# 5_to_12v_stepup.net
KiCad netlist of a schematic drawn in EAGLE
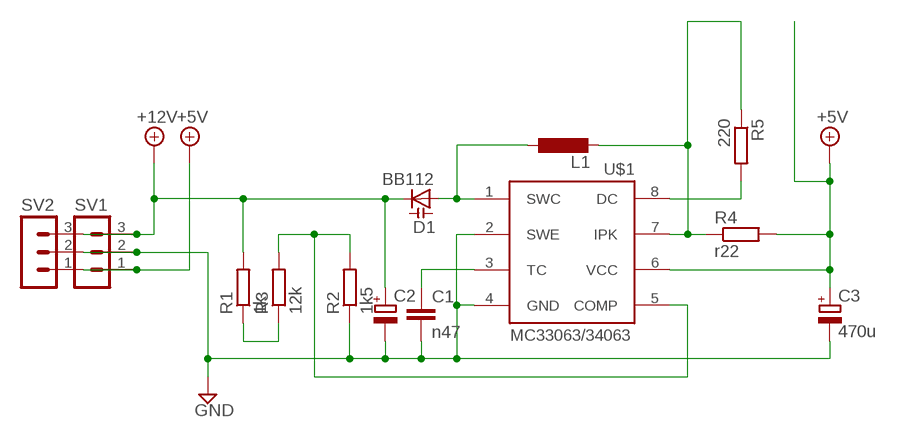
[diagram p0: schematic, sheet 1]

(export (version "E")
  (design (tool "Eeschema 10.0.6"))
  (components
    (comp (ref "C1")
      (value "n47")
      (footprint "eagle-import:C025-025X050")
      (libsource (lib "eagle-import") (part "C-EU025-025X050"))
    )
    (comp (ref "C2")
      (value "CPOL-EUE3.5-8")
      (footprint "eagle-import:E3,5-8")
      (libsource (lib "eagle-import") (part "CPOL-EUE3.5-8"))
    )
    (comp (ref "C3")
      (value "470u")
      (footprint "eagle-import:E3,5-8")
      (libsource (lib "eagle-import") (part "CPOL-EUE3.5-8"))
    )
    (comp (ref "D1")
      (value "BB112")
      (footprint "eagle-import:SOT54H")
      (libsource (lib "eagle-import") (part "BB112"))
    )
    (comp (ref "L1")
      (value "L-EU0207/2V")
      (footprint "eagle-import:0207_2V")
      (libsource (lib "eagle-import") (part "L-EU0207/2V"))
    )
    (comp (ref "R1")
      (value "1k")
      (footprint "eagle-import:0207_2V")
      (libsource (lib "eagle-import") (part "R-EU_0207/2V"))
    )
    (comp (ref "R2")
      (value "1k5")
      (footprint "eagle-import:0207_2V")
      (libsource (lib "eagle-import") (part "R-EU_0207/2V"))
    )
    (comp (ref "R3")
      (value "12k")
      (footprint "eagle-import:0207_2V")
      (libsource (lib "eagle-import") (part "R-EU_0207/2V"))
    )
    (comp (ref "R4")
      (value "r22")
      (footprint "eagle-import:0207_2V")
      (libsource (lib "eagle-import") (part "R-EU_0207/2V"))
    )
    (comp (ref "R5")
      (value "220")
      (footprint "eagle-import:0207_2V")
      (libsource (lib "eagle-import") (part "R-EU_0207/2V"))
    )
    (comp (ref "SV1")
      (value "MA03-1")
      (footprint "eagle-import:MA03-1")
      (libsource (lib "eagle-import") (part "MA03-1"))
    )
    (comp (ref "SV2")
      (value "MA03-1")
      (footprint "eagle-import:MA03-1")
      (libsource (lib "eagle-import") (part "MA03-1"))
    )
    (comp (ref "U$1")
      (value "MC33063/MC34063P")
      (footprint "eagle-import:DIL08")
      (libsource (lib "eagle-import") (part "MC33063/MC34063P"))
    )
  )
  (nets
    (net (code "1") (name "+5V") (class "Default")
      (node (ref "C3") (pin "+") (pinfunction "+_+") (pintype "passive"))
      (node (ref "R4") (pin "2") (pinfunction "2_2") (pintype "passive"))
      (node (ref "SV1") (pin "1") (pinfunction "1_1") (pintype "passive"))
      (node (ref "SV2") (pin "1") (pinfunction "1_1") (pintype "passive"))
      (node (ref "U$1") (pin "6") (pinfunction "VCC_6") (pintype "power_in"))
    )
    (net (code "2") (name "+12V") (class "Default")
      (node (ref "C2") (pin "+") (pinfunction "+_+") (pintype "passive"))
      (node (ref "D1") (pin "C") (pinfunction "C_C") (pintype "passive"))
      (node (ref "R1") (pin "2") (pinfunction "2_2") (pintype "passive"))
      (node (ref "SV1") (pin "3") (pinfunction "3_3") (pintype "passive"))
      (node (ref "SV2") (pin "3") (pinfunction "3_3") (pintype "passive"))
    )
    (net (code "3") (name "GND") (class "Default")
      (node (ref "C1") (pin "2") (pinfunction "2_2") (pintype "passive"))
      (node (ref "C2") (pin "-") (pinfunction "-_-") (pintype "passive"))
      (node (ref "C3") (pin "-") (pinfunction "-_-") (pintype "passive"))
      (node (ref "R2") (pin "1") (pinfunction "1_1") (pintype "passive"))
      (node (ref "SV1") (pin "2") (pinfunction "2_2") (pintype "passive"))
      (node (ref "SV2") (pin "2") (pinfunction "2_2") (pintype "passive"))
      (node (ref "U$1") (pin "2") (pinfunction "SWE_2") (pintype "input"))
      (node (ref "U$1") (pin "4") (pinfunction "GND_4") (pintype "power_in"))
    )
    (net (code "4") (name "Net-(R1-Pad1)") (class "Default")
      (node (ref "R1") (pin "1") (pinfunction "1_1") (pintype "passive"))
      (node (ref "R3") (pin "1") (pinfunction "1_1") (pintype "passive"))
    )
    (net (code "5") (name "Net-(U$1-COMP)") (class "Default")
      (node (ref "R2") (pin "2") (pinfunction "2_2") (pintype "passive"))
      (node (ref "R3") (pin "2") (pinfunction "2_2") (pintype "passive"))
      (node (ref "U$1") (pin "5") (pinfunction "COMP_5") (pintype "input"))
    )
    (net (code "6") (name "Net-(U$1-DC)") (class "Default")
      (node (ref "R5") (pin "2") (pinfunction "2_2") (pintype "passive"))
      (node (ref "U$1") (pin "8") (pinfunction "DC_8") (pintype "input"))
    )
    (net (code "7") (name "Net-(U$1-IPK)") (class "Default")
      (node (ref "L1") (pin "2") (pinfunction "2_2") (pintype "passive"))
      (node (ref "R4") (pin "1") (pinfunction "1_1") (pintype "passive"))
      (node (ref "R5") (pin "1") (pinfunction "1_1") (pintype "passive"))
      (node (ref "U$1") (pin "7") (pinfunction "IPK_7") (pintype "bidirectional"))
    )
    (net (code "8") (name "Net-(U$1-SWC)") (class "Default")
      (node (ref "D1") (pin "A") (pinfunction "A_A") (pintype "passive"))
      (node (ref "L1") (pin "1") (pinfunction "1_1") (pintype "passive"))
      (node (ref "U$1") (pin "1") (pinfunction "SWC_1") (pintype "input"))
    )
    (net (code "9") (name "Net-(U$1-TC)") (class "Default")
      (node (ref "C1") (pin "1") (pinfunction "1_1") (pintype "passive"))
      (node (ref "U$1") (pin "3") (pinfunction "TC_3") (pintype "input"))
    )
  )
)
